# Audio.net
KiCad netlist of a schematic drawn in Altium Designer
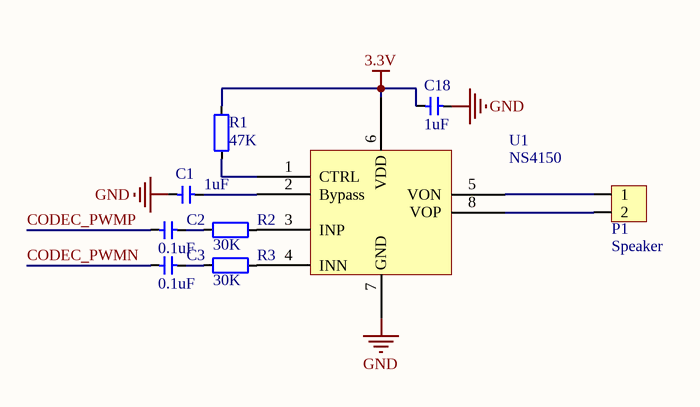
[diagram p0: Audio.SchDoc]

(export (version "E")
  (design (tool "Eeschema 10.0.6"))
  (components
    (comp (ref "C1")
      (value "1uF")
      (footprint "PCB_PassiveCap:CAP_0402")
      (description "Capacitor")
      (fields (field (name "Comment") "Cap_0402"))
      (libsource (lib "SCH_Passive") (part "Cap_0402"))
    )
    (comp (ref "C2")
      (value "0.1uF")
      (footprint "PCB_PassiveCap:CAP_0402")
      (description "Capacitor")
      (fields (field (name "Comment") "Cap_0402"))
      (libsource (lib "SCH_Passive") (part "Cap_0402"))
    )
    (comp (ref "C3")
      (value "0.1uF")
      (footprint "PCB_PassiveCap:CAP_0402")
      (description "Capacitor")
      (fields (field (name "Comment") "Cap_0402"))
      (libsource (lib "SCH_Passive") (part "Cap_0402"))
    )
    (comp (ref "C18")
      (value "1uF")
      (footprint "PCB_PassiveCap:CAP_0402")
      (description "Capacitor")
      (fields (field (name "Comment") "Cap_0402"))
      (libsource (lib "SCH_Passive") (part "Cap_0402"))
    )
    (comp (ref "P1")
      (value "Speaker")
      (footprint "PCB_ConnectorHDR:HDR1X2_2.54_180")
      (description "Header")
      (libsource (lib "SCH_ConnectorHDR") (part "HDR1x2_2.54"))
    )
    (comp (ref "R1")
      (value "47K")
      (footprint "PCB_PassiveRes:RES_0402")
      (description "Resistor")
      (fields (field (name "Comment") "Res_0402"))
      (libsource (lib "") (part "Res_0402_1"))
    )
    (comp (ref "R2")
      (value "30K")
      (footprint "PCB_PassiveRes:RES_0402")
      (description "Resistor")
      (fields (field (name "Comment") "Res_0402"))
      (libsource (lib "SCH_Passive") (part "Res_0402"))
    )
    (comp (ref "R3")
      (value "30K")
      (footprint "PCB_PassiveRes:RES_0402")
      (description "Resistor")
      (fields (field (name "Comment") "Res_0402"))
      (libsource (lib "SCH_Passive") (part "Res_0402"))
    )
    (comp (ref "U1")
      (value "NS4150")
      (footprint "SOP_E150_8")
      (description "D Class Audio Amp")
      (libsource (lib "SCH_IntegratedCircuit") (part "NS4150"))
    )
  )
  (nets
    (net (code "1") (name "/CODEC_PWMN") (class "Default")
      (node (ref "C3") (pin "1") (pinfunction "1_1") (pintype "passive"))
    )
    (net (code "2") (name "/CODEC_PWMP") (class "Default")
      (node (ref "C2") (pin "1") (pinfunction "1_1") (pintype "passive"))
    )
    (net (code "3") (name "3.3V") (class "Default")
      (node (ref "C18") (pin "2") (pinfunction "2_2") (pintype "passive"))
      (node (ref "R1") (pin "2") (pinfunction "2_2") (pintype "passive"))
      (node (ref "U1") (pin "6") (pinfunction "VDD_6") (pintype "passive"))
    )
    (net (code "4") (name "GND") (class "Default")
      (node (ref "C1") (pin "1") (pinfunction "1_1") (pintype "passive"))
      (node (ref "C18") (pin "1") (pinfunction "1_1") (pintype "passive"))
    )
    (net (code "5") (name "Net-(C2-Pad2)") (class "Default")
      (node (ref "C2") (pin "2") (pinfunction "2_2") (pintype "passive"))
      (node (ref "R2") (pin "2") (pinfunction "2_2") (pintype "passive"))
    )
    (net (code "6") (name "Net-(C3-Pad2)") (class "Default")
      (node (ref "C3") (pin "2") (pinfunction "2_2") (pintype "passive"))
      (node (ref "R3") (pin "2") (pinfunction "2_2") (pintype "passive"))
    )
    (net (code "7") (name "Net-(U1-Bypass)") (class "Default")
      (node (ref "C1") (pin "2") (pinfunction "2_2") (pintype "passive"))
      (node (ref "U1") (pin "2") (pinfunction "Bypass_2") (pintype "passive"))
    )
    (net (code "8") (name "Net-(U1-CTRL)") (class "Default")
      (node (ref "R1") (pin "1") (pinfunction "1_1") (pintype "passive"))
      (node (ref "U1") (pin "1") (pinfunction "CTRL_1") (pintype "passive"))
    )
    (net (code "9") (name "Net-(U1-INN)") (class "Default")
      (node (ref "R3") (pin "1") (pinfunction "1_1") (pintype "passive"))
      (node (ref "U1") (pin "4") (pinfunction "INN_4") (pintype "passive"))
    )
    (net (code "10") (name "Net-(U1-INP)") (class "Default")
      (node (ref "R2") (pin "1") (pinfunction "1_1") (pintype "passive"))
      (node (ref "U1") (pin "3") (pinfunction "INP_3") (pintype "passive"))
    )
    (net (code "11") (name "Net-(U1-VON)") (class "Default")
      (node (ref "P1") (pin "1") (pinfunction "1_1") (pintype "passive"))
      (node (ref "U1") (pin "5") (pinfunction "VON_5") (pintype "passive"))
    )
    (net (code "12") (name "Net-(U1-VOP)") (class "Default")
      (node (ref "P1") (pin "2") (pinfunction "2_2") (pintype "passive"))
      (node (ref "U1") (pin "8") (pinfunction "VOP_8") (pintype "passive"))
    )
    (net (code "13") (name "unconnected-(U1-GND-Pad7)") (class "Default")
      (node (ref "U1") (pin "7") (pinfunction "GND_7") (pintype "passive"))
    )
  )
)
